# PXMC.net
KiCad netlist of a schematic drawn in Altium Designer
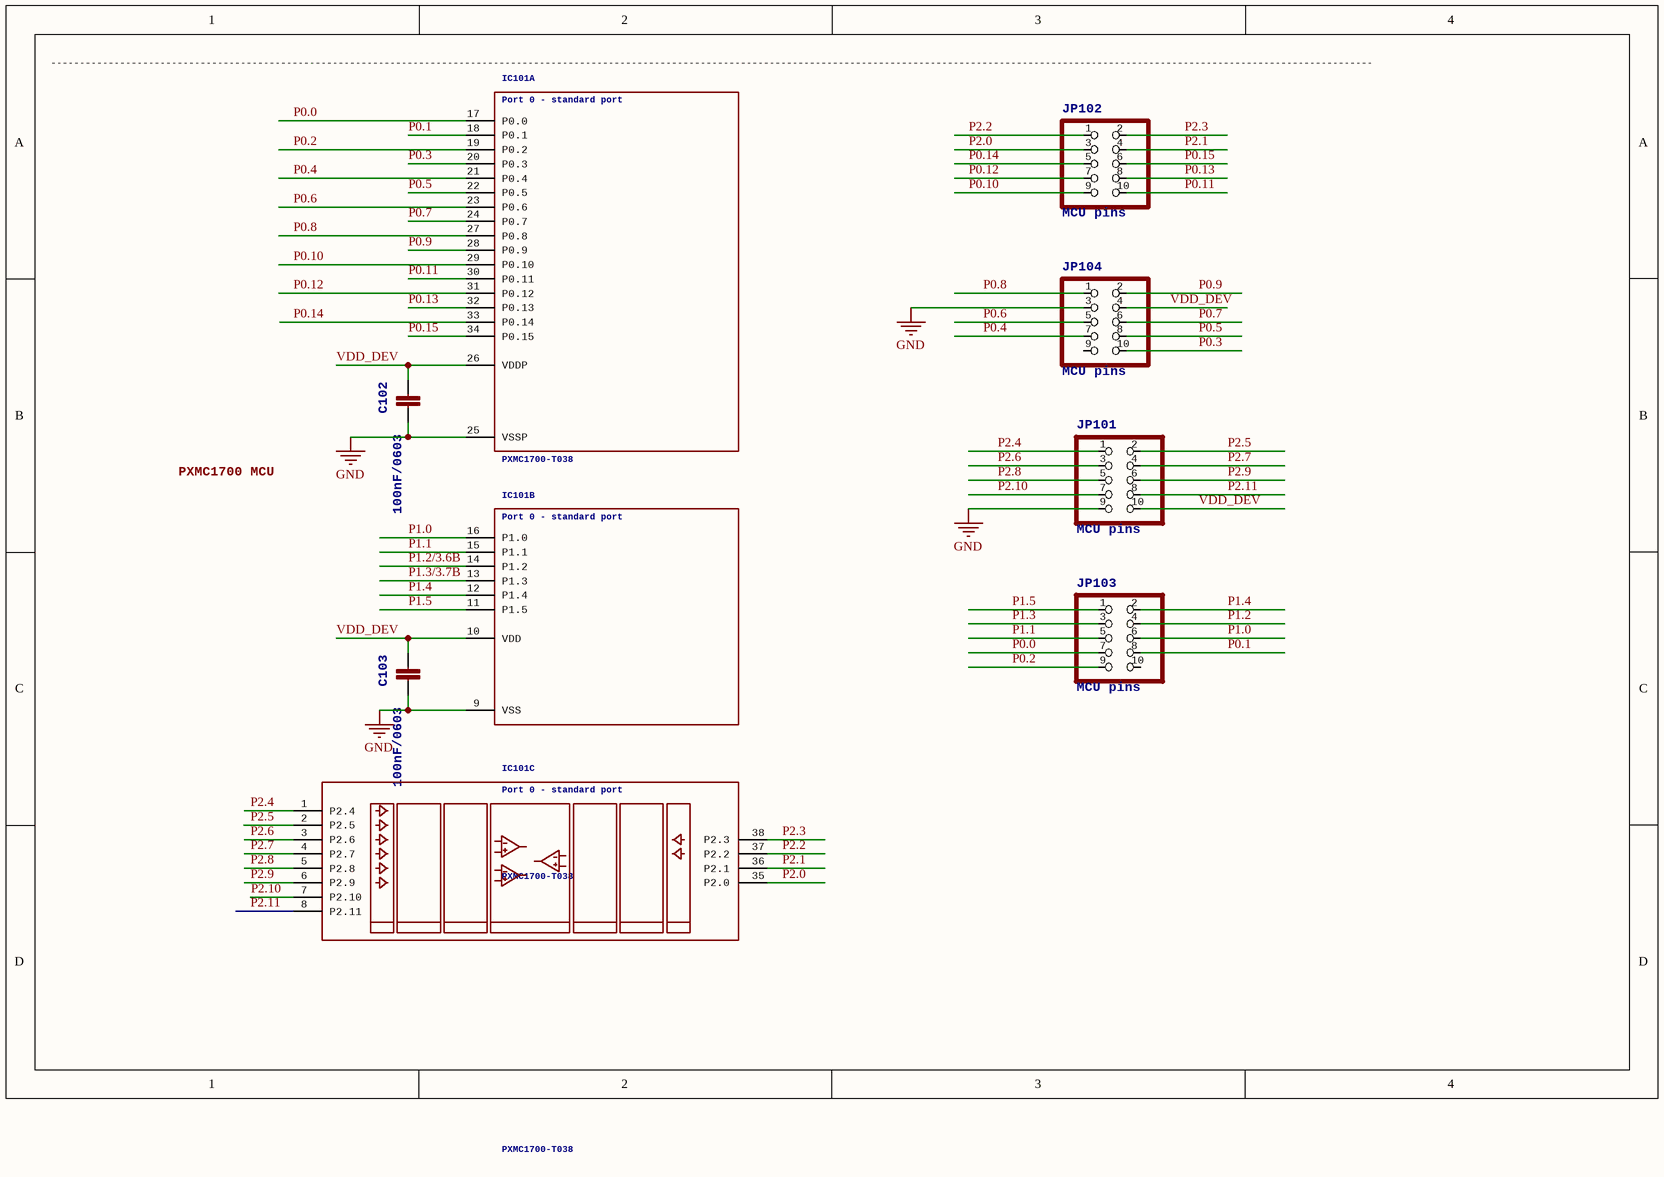
[diagram p0: PXMC.SchDoc]

(export (version "E")
  (design (tool "Eeschema 10.0.6"))
  (components
    (comp (ref "C102")
      (value "100nF/0603")
      (footprint "RCL_C0603")
      (description "CAPACITOR, European symbol")
      (libsource (lib "sucaiku") (part "RCL_C-EUC0603"))
    )
    (comp (ref "C103")
      (value "100nF/0603")
      (footprint "RCL_C0603")
      (description "CAPACITOR, European symbol")
      (libsource (lib "sucaiku") (part "RCL_C-EUC0603"))
    )
    (comp (ref "IC101")
      (value "PXMC1700-T038")
      (footprint "P-TSSOP38-9")
      (fields (field (name "PORT0-STANDARDPORT") "Port 0 - standard port"))
      (libsource (lib "sucaiku") (part "XMC1000-T038"))
    )
    (comp (ref "JP101")
      (value "MCU pins")
      (footprint "2X05")
      (description "PIN HEADER")
      (libsource (lib "sucaiku") (part "PINHD-2X5"))
    )
    (comp (ref "JP102")
      (value "MCU pins")
      (footprint "2X05")
      (description "PIN HEADER")
      (libsource (lib "sucaiku") (part "PINHD-2X5"))
    )
    (comp (ref "JP103")
      (value "MCU pins")
      (footprint "2X05")
      (description "PIN HEADER")
      (libsource (lib "sucaiku") (part "PINHD-2X5"))
    )
    (comp (ref "JP104")
      (value "MCU pins")
      (footprint "2X05")
      (description "PIN HEADER")
      (libsource (lib "sucaiku") (part "PINHD-2X5"))
    )
  )
  (nets
    (net (code "1") (name "/P0.0") (class "Default")
      (node (ref "IC101") (pin "17") (pinfunction "P0.0_17") (pintype "passive"))
      (node (ref "JP103") (pin "7") (pinfunction "7_7") (pintype "passive"))
    )
    (net (code "2") (name "/P0.1") (class "Default")
      (node (ref "IC101") (pin "18") (pinfunction "P0.1_18") (pintype "passive"))
      (node (ref "JP103") (pin "8") (pinfunction "8_8") (pintype "passive"))
    )
    (net (code "3") (name "/P0.2") (class "Default")
      (node (ref "IC101") (pin "19") (pinfunction "P0.2_19") (pintype "passive"))
      (node (ref "JP103") (pin "9") (pinfunction "9_9") (pintype "passive"))
    )
    (net (code "4") (name "/P0.3") (class "Default")
      (node (ref "IC101") (pin "20") (pinfunction "P0.3_20") (pintype "passive"))
      (node (ref "JP104") (pin "10") (pinfunction "10_10") (pintype "passive"))
    )
    (net (code "5") (name "/P0.4") (class "Default")
      (node (ref "IC101") (pin "21") (pinfunction "P0.4_21") (pintype "passive"))
      (node (ref "JP104") (pin "7") (pinfunction "7_7") (pintype "passive"))
    )
    (net (code "6") (name "/P0.5") (class "Default")
      (node (ref "IC101") (pin "22") (pinfunction "P0.5_22") (pintype "passive"))
      (node (ref "JP104") (pin "8") (pinfunction "8_8") (pintype "passive"))
    )
    (net (code "7") (name "/P0.6") (class "Default")
      (node (ref "IC101") (pin "23") (pinfunction "P0.6_23") (pintype "passive"))
      (node (ref "JP104") (pin "5") (pinfunction "5_5") (pintype "passive"))
    )
    (net (code "8") (name "/P0.7") (class "Default")
      (node (ref "IC101") (pin "24") (pinfunction "P0.7_24") (pintype "passive"))
      (node (ref "JP104") (pin "6") (pinfunction "6_6") (pintype "passive"))
    )
    (net (code "9") (name "/P0.8") (class "Default")
      (node (ref "IC101") (pin "27") (pinfunction "P0.8_27") (pintype "passive"))
      (node (ref "JP104") (pin "1") (pinfunction "1_1") (pintype "passive"))
    )
    (net (code "10") (name "/P0.9") (class "Default")
      (node (ref "IC101") (pin "28") (pinfunction "P0.9_28") (pintype "passive"))
      (node (ref "JP104") (pin "2") (pinfunction "2_2") (pintype "passive"))
    )
    (net (code "11") (name "/P0.10") (class "Default")
      (node (ref "IC101") (pin "29") (pinfunction "P0.10_29") (pintype "passive"))
      (node (ref "JP102") (pin "9") (pinfunction "9_9") (pintype "passive"))
    )
    (net (code "12") (name "/P0.11") (class "Default")
      (node (ref "IC101") (pin "30") (pinfunction "P0.11_30") (pintype "passive"))
      (node (ref "JP102") (pin "10") (pinfunction "10_10") (pintype "passive"))
    )
    (net (code "13") (name "/P0.12") (class "Default")
      (node (ref "IC101") (pin "31") (pinfunction "P0.12_31") (pintype "passive"))
      (node (ref "JP102") (pin "7") (pinfunction "7_7") (pintype "passive"))
    )
    (net (code "14") (name "/P0.13") (class "Default")
      (node (ref "IC101") (pin "32") (pinfunction "P0.13_32") (pintype "passive"))
      (node (ref "JP102") (pin "8") (pinfunction "8_8") (pintype "passive"))
    )
    (net (code "15") (name "/P0.14") (class "Default")
      (node (ref "IC101") (pin "33") (pinfunction "P0.14_33") (pintype "passive"))
      (node (ref "JP102") (pin "5") (pinfunction "5_5") (pintype "passive"))
    )
    (net (code "16") (name "/P0.15") (class "Default")
      (node (ref "IC101") (pin "34") (pinfunction "P0.15_34") (pintype "passive"))
      (node (ref "JP102") (pin "6") (pinfunction "6_6") (pintype "passive"))
    )
    (net (code "17") (name "/P1.0") (class "Default")
      (node (ref "IC101") (pin "16") (pinfunction "P1.0_16") (pintype "passive"))
      (node (ref "JP103") (pin "6") (pinfunction "6_6") (pintype "passive"))
    )
    (net (code "18") (name "/P1.1") (class "Default")
      (node (ref "IC101") (pin "15") (pinfunction "P1.1_15") (pintype "passive"))
      (node (ref "JP103") (pin "5") (pinfunction "5_5") (pintype "passive"))
    )
    (net (code "19") (name "/P1.2") (class "Default")
      (node (ref "JP103") (pin "4") (pinfunction "4_4") (pintype "passive"))
    )
    (net (code "20") (name "/P1.2{slash}3.6B") (class "Default")
      (node (ref "IC101") (pin "14") (pinfunction "P1.2_14") (pintype "passive"))
    )
    (net (code "21") (name "/P1.3") (class "Default")
      (node (ref "JP103") (pin "3") (pinfunction "3_3") (pintype "passive"))
    )
    (net (code "22") (name "/P1.3{slash}3.7B") (class "Default")
      (node (ref "IC101") (pin "13") (pinfunction "P1.3_13") (pintype "passive"))
    )
    (net (code "23") (name "/P1.4") (class "Default")
      (node (ref "IC101") (pin "12") (pinfunction "P1.4_12") (pintype "passive"))
      (node (ref "JP103") (pin "2") (pinfunction "2_2") (pintype "passive"))
    )
    (net (code "24") (name "/P1.5") (class "Default")
      (node (ref "IC101") (pin "11") (pinfunction "P1.5_11") (pintype "passive"))
      (node (ref "JP103") (pin "1") (pinfunction "1_1") (pintype "passive"))
    )
    (net (code "25") (name "/P2.0") (class "Default")
      (node (ref "IC101") (pin "35") (pinfunction "P2.0_35") (pintype "passive"))
      (node (ref "JP102") (pin "3") (pinfunction "3_3") (pintype "passive"))
    )
    (net (code "26") (name "/P2.1") (class "Default")
      (node (ref "IC101") (pin "36") (pinfunction "P2.1_36") (pintype "passive"))
      (node (ref "JP102") (pin "4") (pinfunction "4_4") (pintype "passive"))
    )
    (net (code "27") (name "/P2.2") (class "Default")
      (node (ref "IC101") (pin "37") (pinfunction "P2.2_37") (pintype "passive"))
      (node (ref "JP102") (pin "1") (pinfunction "1_1") (pintype "passive"))
    )
    (net (code "28") (name "/P2.3") (class "Default")
      (node (ref "IC101") (pin "38") (pinfunction "P2.3_38") (pintype "passive"))
      (node (ref "JP102") (pin "2") (pinfunction "2_2") (pintype "passive"))
    )
    (net (code "29") (name "/P2.4") (class "Default")
      (node (ref "IC101") (pin "1") (pinfunction "P2.4_1") (pintype "passive"))
      (node (ref "JP101") (pin "1") (pinfunction "1_1") (pintype "passive"))
    )
    (net (code "30") (name "/P2.5") (class "Default")
      (node (ref "IC101") (pin "2") (pinfunction "P2.5_2") (pintype "passive"))
      (node (ref "JP101") (pin "2") (pinfunction "2_2") (pintype "passive"))
    )
    (net (code "31") (name "/P2.6") (class "Default")
      (node (ref "IC101") (pin "3") (pinfunction "P2.6_3") (pintype "passive"))
      (node (ref "JP101") (pin "3") (pinfunction "3_3") (pintype "passive"))
    )
    (net (code "32") (name "/P2.7") (class "Default")
      (node (ref "IC101") (pin "4") (pinfunction "P2.7_4") (pintype "passive"))
      (node (ref "JP101") (pin "4") (pinfunction "4_4") (pintype "passive"))
    )
    (net (code "33") (name "/P2.8") (class "Default")
      (node (ref "IC101") (pin "5") (pinfunction "P2.8_5") (pintype "passive"))
      (node (ref "JP101") (pin "5") (pinfunction "5_5") (pintype "passive"))
    )
    (net (code "34") (name "/P2.9") (class "Default")
      (node (ref "IC101") (pin "6") (pinfunction "P2.9_6") (pintype "passive"))
      (node (ref "JP101") (pin "6") (pinfunction "6_6") (pintype "passive"))
    )
    (net (code "35") (name "/P2.10") (class "Default")
      (node (ref "IC101") (pin "7") (pinfunction "P2.10_7") (pintype "passive"))
      (node (ref "JP101") (pin "7") (pinfunction "7_7") (pintype "passive"))
    )
    (net (code "36") (name "/P2.11") (class "Default")
      (node (ref "IC101") (pin "8") (pinfunction "P2.11_8") (pintype "passive"))
      (node (ref "JP101") (pin "8") (pinfunction "8_8") (pintype "passive"))
    )
    (net (code "37") (name "/VDD_DEV") (class "Default")
      (node (ref "C102") (pin "1") (pinfunction "1_1") (pintype "passive"))
      (node (ref "C103") (pin "1") (pinfunction "1_1") (pintype "passive"))
      (node (ref "IC101") (pin "10") (pinfunction "VDD_10") (pintype "power_in"))
      (node (ref "IC101") (pin "26") (pinfunction "VDDP_26") (pintype "power_in"))
      (node (ref "JP101") (pin "10") (pinfunction "10_10") (pintype "passive"))
      (node (ref "JP104") (pin "4") (pinfunction "4_4") (pintype "passive"))
    )
    (net (code "38") (name "GND") (class "Default")
      (node (ref "C102") (pin "2") (pinfunction "2_2") (pintype "passive"))
      (node (ref "C103") (pin "2") (pinfunction "2_2") (pintype "passive"))
      (node (ref "IC101") (pin "25") (pinfunction "VSSP_25") (pintype "power_in"))
      (node (ref "IC101") (pin "9") (pinfunction "VSS_9") (pintype "power_in"))
      (node (ref "JP101") (pin "9") (pinfunction "9_9") (pintype "passive"))
      (node (ref "JP104") (pin "3") (pinfunction "3_3") (pintype "passive"))
    )
    (net (code "39") (name "unconnected-(JP103-Pad10)") (class "Default")
      (node (ref "JP103") (pin "10") (pinfunction "10_10") (pintype "passive"))
    )
    (net (code "40") (name "unconnected-(JP104-Pad9)") (class "Default")
      (node (ref "JP104") (pin "9") (pinfunction "9_9") (pintype "passive"))
    )
  )
)
